# wifi-amp.net
KiCad netlist of a schematic drawn in EAGLE
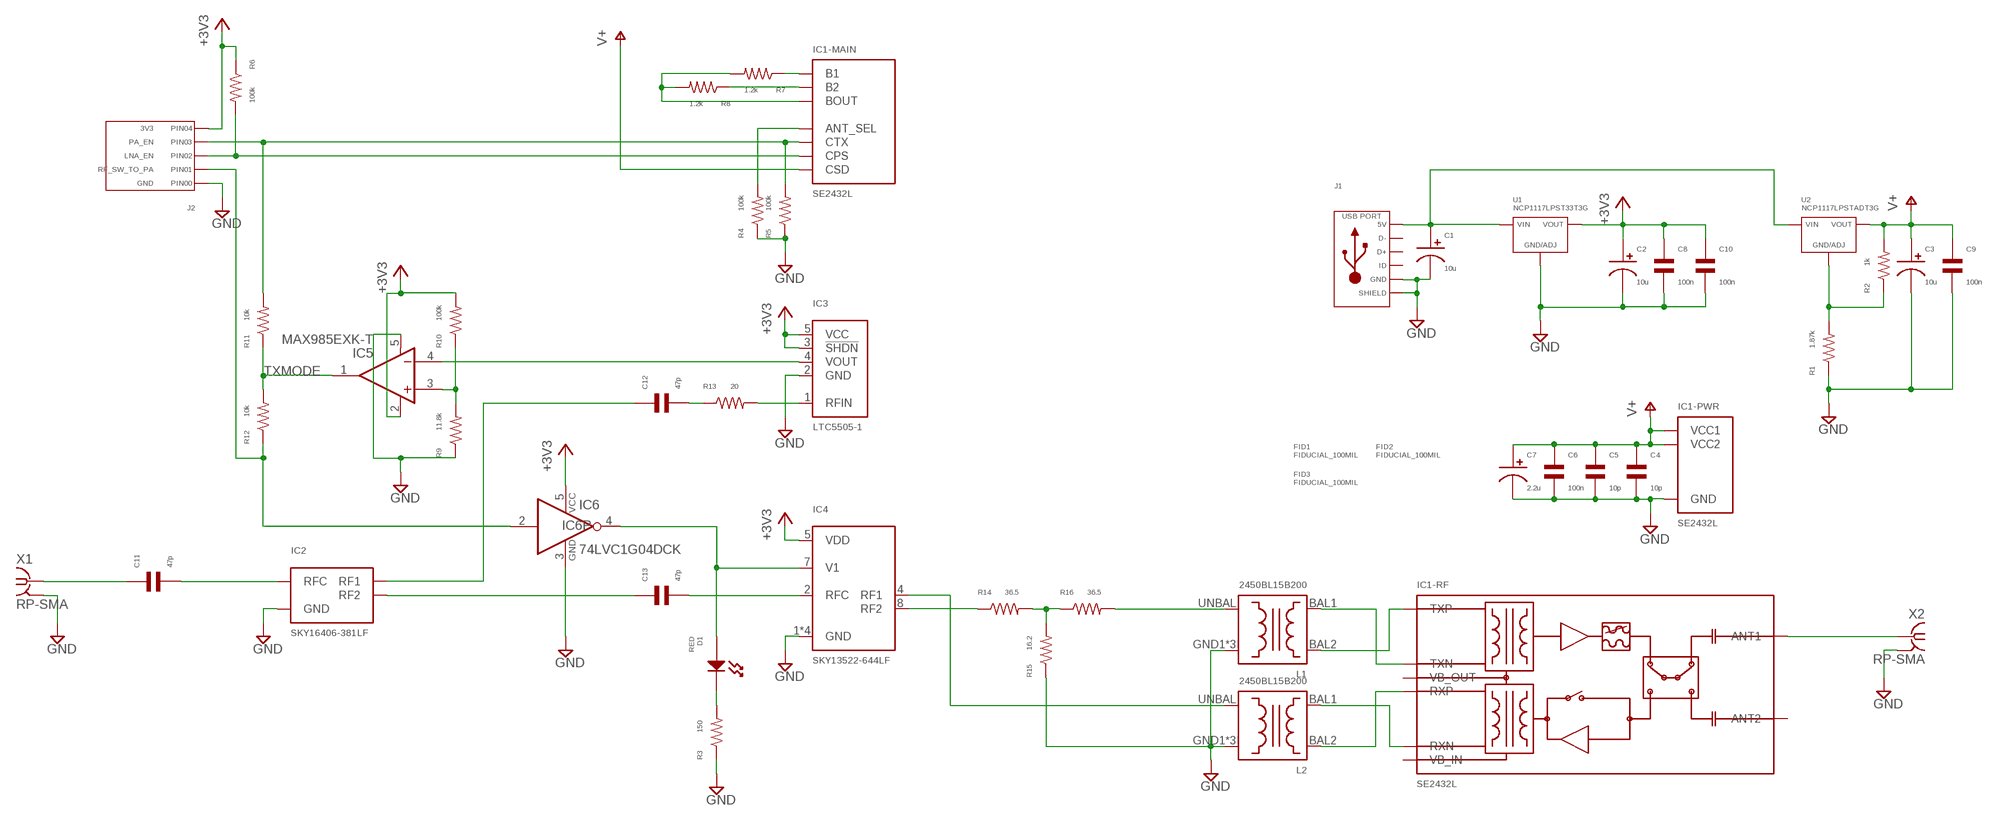
[diagram p0: schematic, sheet 1]

(export (version "E")
  (design (tool "Eeschema 10.0.6"))
  (components
    (comp (ref "C1")
      (value "10u")
      (footprint "eagle-import:CP4MM")
      (libsource (lib "eagle-import") (part "CAPACITOR_P_4MM"))
    )
    (comp (ref "C2")
      (value "10u")
      (footprint "eagle-import:CP4MM")
      (libsource (lib "eagle-import") (part "CAPACITOR_P_4MM"))
    )
    (comp (ref "C3")
      (value "10u")
      (footprint "eagle-import:CP4MM")
      (libsource (lib "eagle-import") (part "CAPACITOR_P_4MM"))
    )
    (comp (ref "C4")
      (value "10p")
      (footprint "eagle-import:C0402")
      (libsource (lib "eagle-import") (part "CAPACITOR_NP_0402"))
    )
    (comp (ref "C5")
      (value "10p")
      (footprint "eagle-import:C0402")
      (libsource (lib "eagle-import") (part "CAPACITOR_NP_0402"))
    )
    (comp (ref "C6")
      (value "100n")
      (footprint "eagle-import:C0402")
      (libsource (lib "eagle-import") (part "CAPACITOR_NP_0402"))
    )
    (comp (ref "C7")
      (value "2.2u")
      (footprint "eagle-import:CP4MM")
      (libsource (lib "eagle-import") (part "CAPACITOR_P_4MM"))
    )
    (comp (ref "C8")
      (value "100n")
      (footprint "eagle-import:C0402")
      (libsource (lib "eagle-import") (part "CAPACITOR_NP_0402"))
    )
    (comp (ref "C9")
      (value "100n")
      (footprint "eagle-import:C0402")
      (libsource (lib "eagle-import") (part "CAPACITOR_NP_0402"))
    )
    (comp (ref "C10")
      (value "100n")
      (footprint "eagle-import:C0402")
      (libsource (lib "eagle-import") (part "CAPACITOR_NP_0402"))
    )
    (comp (ref "C11")
      (value "47p")
      (footprint "eagle-import:C0402")
      (libsource (lib "eagle-import") (part "CAPACITOR_NP_0402"))
    )
    (comp (ref "C12")
      (value "47p")
      (footprint "eagle-import:C0402")
      (libsource (lib "eagle-import") (part "CAPACITOR_NP_0402"))
    )
    (comp (ref "C13")
      (value "47p")
      (footprint "eagle-import:C0402")
      (libsource (lib "eagle-import") (part "CAPACITOR_NP_0402"))
    )
    (comp (ref "D1")
      (value "RED")
      (footprint "eagle-import:LED0603")
      (libsource (lib "eagle-import") (part "LED_SINGLE_0603"))
    )
    (comp (ref "FID1")
      (value "FIDUCIAL_100MIL")
      (footprint "eagle-import:FIDUCIAL_100MIL")
      (libsource (lib "eagle-import") (part "FIDUCIAL_100MIL"))
    )
    (comp (ref "FID2")
      (value "FIDUCIAL_100MIL")
      (footprint "eagle-import:FIDUCIAL_100MIL")
      (libsource (lib "eagle-import") (part "FIDUCIAL_100MIL"))
    )
    (comp (ref "FID3")
      (value "FIDUCIAL_100MIL")
      (footprint "eagle-import:FIDUCIAL_100MIL")
      (libsource (lib "eagle-import") (part "FIDUCIAL_100MIL"))
    )
    (comp (ref "IC1")
      (value "SE2432L")
      (footprint "eagle-import:24QFN")
      (libsource (lib "eagle-import") (part "SE2432L"))
    )
    (comp (ref "IC2")
      (value "SKY16406-381LF")
      (footprint "eagle-import:DFN6")
      (libsource (lib "eagle-import") (part "SKY16406-381LF"))
    )
    (comp (ref "IC3")
      (value "LTC5505-1")
      (footprint "eagle-import:SOT23-5")
      (libsource (lib "eagle-import") (part "LTC5505"))
    )
    (comp (ref "IC4")
      (value "SKY13522-644LF")
      (footprint "eagle-import:QFN8")
      (libsource (lib "eagle-import") (part "SKY13522-644LF"))
    )
    (comp (ref "IC5")
      (value "MAX985EXK-T")
      (footprint "eagle-import:SC70-5L")
      (fields (field (name "MPN") "MAX986EXK+T"))
      (libsource (lib "eagle-import") (part "MAX98EXK-T6"))
    )
    (comp (ref "IC6")
      (value "74LVC1G04DCK")
      (footprint "eagle-import:SC70-5")
      (libsource (lib "eagle-import") (part "741G04DCKLVC"))
    )
    (comp (ref "J1")
      (value "USB_MICRO_RIGHT")
      (footprint "eagle-import:MICROUSB-RIGHT")
      (libsource (lib "eagle-import") (part "USB_MICRO_RIGHT"))
    )
    (comp (ref "J2")
      (value "HEADER_01X05_PTH_2.54MM")
      (footprint "eagle-import:PTH_2.54MM_01X05")
      (fields
        (field (name "LABEL00") "GND")
        (field (name "LABEL01") "RF_SW_TO_PA")
        (field (name "LABEL02") "LNA_EN")
        (field (name "LABEL03") "PA_EN")
        (field (name "LABEL04") "3V3")
      )
      (libsource (lib "eagle-import") (part "HEADER_01X05_PTH_2.54MM"))
    )
    (comp (ref "L1")
      (value "2450BL15B200")
      (footprint "eagle-import:2450BL15B200")
      (libsource (lib "eagle-import") (part "2450BL15B200"))
    )
    (comp (ref "L2")
      (value "2450BL15B200")
      (footprint "eagle-import:2450BL15B200")
      (libsource (lib "eagle-import") (part "2450BL15B200"))
    )
    (comp (ref "R1")
      (value "1.87k")
      (footprint "eagle-import:R0805")
      (fields (field (name "TOLERANCE") "1%"))
      (libsource (lib "eagle-import") (part "RESISTOR_0805"))
    )
    (comp (ref "R2")
      (value "1k")
      (footprint "eagle-import:R0805")
      (fields (field (name "TOLERANCE") "1%"))
      (libsource (lib "eagle-import") (part "RESISTOR_0805"))
    )
    (comp (ref "R3")
      (value "150")
      (footprint "eagle-import:R0402")
      (fields (field (name "TOLERANCE") "1%"))
      (libsource (lib "eagle-import") (part "RESISTOR_0402"))
    )
    (comp (ref "R4")
      (value "100k")
      (footprint "eagle-import:R0402")
      (libsource (lib "eagle-import") (part "RESISTOR_0402"))
    )
    (comp (ref "R5")
      (value "100k")
      (footprint "eagle-import:R0402")
      (libsource (lib "eagle-import") (part "RESISTOR_0402"))
    )
    (comp (ref "R6")
      (value "100k")
      (footprint "eagle-import:R0402")
      (libsource (lib "eagle-import") (part "RESISTOR_0402"))
    )
    (comp (ref "R7")
      (value "1.2k")
      (footprint "eagle-import:R0402")
      (fields (field (name "TOLERANCE") "1%"))
      (libsource (lib "eagle-import") (part "RESISTOR_0402"))
    )
    (comp (ref "R8")
      (value "1.2k")
      (footprint "eagle-import:R0402")
      (fields (field (name "TOLERANCE") "1%"))
      (libsource (lib "eagle-import") (part "RESISTOR_0402"))
    )
    (comp (ref "R9")
      (value "11.8k")
      (footprint "eagle-import:R0402")
      (fields (field (name "TOLERANCE") "1%"))
      (libsource (lib "eagle-import") (part "RESISTOR_0402"))
    )
    (comp (ref "R10")
      (value "100k")
      (footprint "eagle-import:R0402")
      (fields (field (name "TOLERANCE") "1%"))
      (libsource (lib "eagle-import") (part "RESISTOR_0402"))
    )
    (comp (ref "R11")
      (value "10k")
      (footprint "eagle-import:R0402")
      (libsource (lib "eagle-import") (part "RESISTOR_0402"))
    )
    (comp (ref "R12")
      (value "10k")
      (footprint "eagle-import:R0402")
      (libsource (lib "eagle-import") (part "RESISTOR_0402"))
    )
    (comp (ref "R13")
      (value "20")
      (footprint "eagle-import:R0402")
      (fields (field (name "TOLERANCE") "1%"))
      (libsource (lib "eagle-import") (part "RESISTOR_0402"))
    )
    (comp (ref "R14")
      (value "36.5")
      (footprint "eagle-import:R0402")
      (fields (field (name "TOLERANCE") "1%"))
      (libsource (lib "eagle-import") (part "RESISTOR_0402"))
    )
    (comp (ref "R15")
      (value "16.2")
      (footprint "eagle-import:R0402")
      (fields (field (name "TOLERANCE") "1%"))
      (libsource (lib "eagle-import") (part "RESISTOR_0402"))
    )
    (comp (ref "R16")
      (value "36.5")
      (footprint "eagle-import:R0402")
      (fields (field (name "TOLERANCE") "1%"))
      (libsource (lib "eagle-import") (part "RESISTOR_0402"))
    )
    (comp (ref "U1")
      (value "NCP1117LPST33T3G")
      (footprint "eagle-import:SOT-223-3")
      (libsource (lib "eagle-import") (part "NCP1117LPST33T3G"))
    )
    (comp (ref "U2")
      (value "NCP1117LPSTADT3G")
      (footprint "eagle-import:SOT-223-3")
      (libsource (lib "eagle-import") (part "NCP1117LPSTADT3G"))
    )
    (comp (ref "X1")
      (value "RP-SMA")
      (footprint "eagle-import:BU-SMA-H")
      (libsource (lib "eagle-import") (part "BU-SMA-H"))
    )
    (comp (ref "X2")
      (value "RP-SMA")
      (footprint "eagle-import:BU-SMA-H")
      (libsource (lib "eagle-import") (part "BU-SMA-H"))
    )
  )
  (nets
    (net (code "1") (name "+3V3") (class "Default")
      (node (ref "C10") (pin "P$1") (pinfunction "P$1_P$1") (pintype "passive"))
      (node (ref "C2") (pin "P$1") (pinfunction "P$1_P$1") (pintype "passive"))
      (node (ref "C8") (pin "P$1") (pinfunction "P$1_P$1") (pintype "passive"))
      (node (ref "IC3") (pin "3") (pinfunction "~{SHDN}_3") (pintype "bidirectional"))
      (node (ref "IC3") (pin "5") (pinfunction "VCC_5") (pintype "bidirectional"))
      (node (ref "IC4") (pin "5") (pinfunction "VDD_5") (pintype "bidirectional"))
      (node (ref "IC5") (pin "2") (pinfunction "V+_2") (pintype "power_in"))
      (node (ref "IC6") (pin "5") (pinfunction "VCC_5") (pintype "power_in"))
      (node (ref "J2") (pin "P$5") (pinfunction "PIN4_P$5") (pintype "bidirectional"))
      (node (ref "R10") (pin "P$2") (pinfunction "P$2_P$2") (pintype "passive"))
      (node (ref "R6") (pin "P$1") (pinfunction "P$1_P$1") (pintype "passive"))
      (node (ref "U1") (pin "P$1") (pinfunction "VOUT_P$1") (pintype "bidirectional"))
      (node (ref "U1") (pin "P$3") (pinfunction "VOUT_P$3") (pintype "bidirectional"))
    )
    (net (code "2") (name "/TXMODE") (class "Default")
      (node (ref "IC5") (pin "1") (pinfunction "OUT_1") (pintype "output"))
      (node (ref "R11") (pin "P$1") (pinfunction "P$1_P$1") (pintype "passive"))
      (node (ref "R12") (pin "P$2") (pinfunction "P$2_P$2") (pintype "passive"))
    )
    (net (code "3") (name "GND") (class "Default")
      (node (ref "C1") (pin "P$2") (pinfunction "P$2_P$2") (pintype "passive"))
      (node (ref "C10") (pin "P$2") (pinfunction "P$2_P$2") (pintype "passive"))
      (node (ref "C2") (pin "P$2") (pinfunction "P$2_P$2") (pintype "passive"))
      (node (ref "C3") (pin "P$2") (pinfunction "P$2_P$2") (pintype "passive"))
      (node (ref "C4") (pin "P$2") (pinfunction "P$2_P$2") (pintype "passive"))
      (node (ref "C5") (pin "P$2") (pinfunction "P$2_P$2") (pintype "passive"))
      (node (ref "C6") (pin "P$2") (pinfunction "P$2_P$2") (pintype "passive"))
      (node (ref "C7") (pin "P$2") (pinfunction "P$2_P$2") (pintype "passive"))
      (node (ref "C8") (pin "P$2") (pinfunction "P$2_P$2") (pintype "passive"))
      (node (ref "C9") (pin "P$2") (pinfunction "P$2_P$2") (pintype "passive"))
      (node (ref "IC1") (pin "GND1") (pinfunction "GND_GND1") (pintype "bidirectional"))
      (node (ref "IC1") (pin "GND10") (pinfunction "GND_GND10") (pintype "bidirectional"))
      (node (ref "IC1") (pin "GND2") (pinfunction "GND_GND2") (pintype "bidirectional"))
      (node (ref "IC1") (pin "GND3") (pinfunction "GND_GND3") (pintype "bidirectional"))
      (node (ref "IC1") (pin "GND4") (pinfunction "GND_GND4") (pintype "bidirectional"))
      (node (ref "IC1") (pin "GND5") (pinfunction "GND_GND5") (pintype "bidirectional"))
      (node (ref "IC1") (pin "GND6") (pinfunction "GND_GND6") (pintype "bidirectional"))
      (node (ref "IC1") (pin "GND7") (pinfunction "GND_GND7") (pintype "bidirectional"))
      (node (ref "IC1") (pin "GND8") (pinfunction "GND_GND8") (pintype "bidirectional"))
      (node (ref "IC1") (pin "GND9") (pinfunction "GND_GND9") (pintype "bidirectional"))
      (node (ref "IC2") (pin "GND1") (pinfunction "GND_GND1") (pintype "bidirectional"))
      (node (ref "IC2") (pin "GND2") (pinfunction "GND_GND2") (pintype "bidirectional"))
      (node (ref "IC2") (pin "GND3") (pinfunction "GND_GND3") (pintype "bidirectional"))
      (node (ref "IC2") (pin "GNDP") (pinfunction "GND_GNDP") (pintype "bidirectional"))
      (node (ref "IC3") (pin "2") (pinfunction "GND_2") (pintype "bidirectional"))
      (node (ref "IC4") (pin "1") (pinfunction "GND_1") (pintype "bidirectional"))
      (node (ref "IC4") (pin "3") (pinfunction "GND_3") (pintype "bidirectional"))
      (node (ref "IC4") (pin "6") (pinfunction "GND_6") (pintype "bidirectional"))
      (node (ref "IC4") (pin "EP") (pinfunction "GND_EP") (pintype "bidirectional"))
      (node (ref "IC5") (pin "5") (pinfunction "V-_5") (pintype "power_in"))
      (node (ref "IC6") (pin "3") (pinfunction "GND_3") (pintype "power_in"))
      (node (ref "J1") (pin "5") (pinfunction "GND_5") (pintype "power_in"))
      (node (ref "J1") (pin "S1") (pinfunction "SLD_S1") (pintype "power_in"))
      (node (ref "J1") (pin "S2") (pinfunction "SLD_S2") (pintype "power_in"))
      (node (ref "J1") (pin "S3") (pinfunction "SLD_S3") (pintype "power_in"))
      (node (ref "J1") (pin "S4") (pinfunction "SLD_S4") (pintype "power_in"))
      (node (ref "J1") (pin "S5") (pinfunction "SLD_S5") (pintype "power_in"))
      (node (ref "J1") (pin "S6") (pinfunction "SLD_S6") (pintype "power_in"))
      (node (ref "J1") (pin "S7") (pinfunction "SLD_S7") (pintype "power_in"))
      (node (ref "J1") (pin "S8") (pinfunction "SLD_S8") (pintype "power_in"))
      (node (ref "J2") (pin "P$1") (pinfunction "PIN0_P$1") (pintype "bidirectional"))
      (node (ref "L1") (pin "GND1") (pinfunction "GND_GND1") (pintype "bidirectional"))
      (node (ref "L1") (pin "GND2") (pinfunction "GND_GND2") (pintype "bidirectional"))
      (node (ref "L1") (pin "GND3") (pinfunction "GND_GND3") (pintype "bidirectional"))
      (node (ref "L2") (pin "GND1") (pinfunction "GND_GND1") (pintype "bidirectional"))
      (node (ref "L2") (pin "GND2") (pinfunction "GND_GND2") (pintype "bidirectional"))
      (node (ref "L2") (pin "GND3") (pinfunction "GND_GND3") (pintype "bidirectional"))
      (node (ref "R1") (pin "P$1") (pinfunction "P$1_P$1") (pintype "passive"))
      (node (ref "R15") (pin "P$1") (pinfunction "P$1_P$1") (pintype "passive"))
      (node (ref "R3") (pin "P$1") (pinfunction "P$1_P$1") (pintype "passive"))
      (node (ref "R4") (pin "P$1") (pinfunction "P$1_P$1") (pintype "passive"))
      (node (ref "R5") (pin "P$1") (pinfunction "P$1_P$1") (pintype "passive"))
      (node (ref "R9") (pin "P$1") (pinfunction "P$1_P$1") (pintype "passive"))
      (node (ref "U1") (pin "P$2") (pinfunction "GND/ADJ_P$2") (pintype "bidirectional"))
      (node (ref "X1") (pin "2") (pinfunction "2_2") (pintype "passive"))
      (node (ref "X1") (pin "3") (pinfunction "2_3") (pintype "passive"))
      (node (ref "X1") (pin "4") (pinfunction "2_4") (pintype "passive"))
      (node (ref "X1") (pin "5") (pinfunction "2_5") (pintype "passive"))
      (node (ref "X2") (pin "2") (pinfunction "2_2") (pintype "passive"))
      (node (ref "X2") (pin "3") (pinfunction "2_3") (pintype "passive"))
      (node (ref "X2") (pin "4") (pinfunction "2_4") (pintype "passive"))
      (node (ref "X2") (pin "5") (pinfunction "2_5") (pintype "passive"))
    )
    (net (code "4") (name "Net-(C11-PadP$1)") (class "Default")
      (node (ref "C11") (pin "P$1") (pinfunction "P$1_P$1") (pintype "passive"))
      (node (ref "X1") (pin "1") (pinfunction "1_1") (pintype "passive"))
    )
    (net (code "5") (name "Net-(C11-PadP$2)") (class "Default")
      (node (ref "C11") (pin "P$2") (pinfunction "P$2_P$2") (pintype "passive"))
      (node (ref "IC2") (pin "RFC") (pinfunction "RFC_RFC") (pintype "bidirectional"))
    )
    (net (code "6") (name "Net-(C12-PadP$1)") (class "Default")
      (node (ref "C12") (pin "P$1") (pinfunction "P$1_P$1") (pintype "passive"))
      (node (ref "IC2") (pin "RF1") (pinfunction "RF1_RF1") (pintype "bidirectional"))
    )
    (net (code "7") (name "Net-(C12-PadP$2)") (class "Default")
      (node (ref "C12") (pin "P$2") (pinfunction "P$2_P$2") (pintype "passive"))
      (node (ref "R13") (pin "P$1") (pinfunction "P$1_P$1") (pintype "passive"))
    )
    (net (code "8") (name "Net-(C13-PadP$1)") (class "Default")
      (node (ref "C13") (pin "P$1") (pinfunction "P$1_P$1") (pintype "passive"))
      (node (ref "IC2") (pin "RF2") (pinfunction "RF2_RF2") (pintype "bidirectional"))
    )
    (net (code "9") (name "Net-(D1-PadCATHODE)") (class "Default")
      (node (ref "D1") (pin "CATHODE") (pinfunction "CATHODE_CATHODE") (pintype "power_in"))
      (node (ref "R3") (pin "P$2") (pinfunction "P$2_P$2") (pintype "passive"))
    )
    (net (code "10") (name "Net-(IC1-PadANT1)") (class "Default")
      (node (ref "IC1") (pin "ANT1") (pinfunction "ANT1_ANT1") (pintype "bidirectional"))
      (node (ref "X2") (pin "1") (pinfunction "1_1") (pintype "passive"))
    )
    (net (code "11") (name "Net-(IC1-PadANT_SEL)") (class "Default")
      (node (ref "IC1") (pin "ANT_SEL") (pinfunction "ANT_SEL_ANT_SEL") (pintype "bidirectional"))
      (node (ref "R4") (pin "P$2") (pinfunction "P$2_P$2") (pintype "passive"))
    )
    (net (code "12") (name "Net-(IC1-PadB1)") (class "Default")
      (node (ref "IC1") (pin "B1") (pinfunction "B1_B1") (pintype "bidirectional"))
      (node (ref "R7") (pin "P$1") (pinfunction "P$1_P$1") (pintype "passive"))
    )
    (net (code "13") (name "Net-(IC1-PadB2)") (class "Default")
      (node (ref "IC1") (pin "B2") (pinfunction "B2_B2") (pintype "bidirectional"))
      (node (ref "R8") (pin "P$1") (pinfunction "P$1_P$1") (pintype "passive"))
    )
    (net (code "14") (name "Net-(IC1-PadBOUT)") (class "Default")
      (node (ref "IC1") (pin "BOUT") (pinfunction "BOUT_BOUT") (pintype "bidirectional"))
      (node (ref "R7") (pin "P$2") (pinfunction "P$2_P$2") (pintype "passive"))
      (node (ref "R8") (pin "P$2") (pinfunction "P$2_P$2") (pintype "passive"))
    )
    (net (code "15") (name "Net-(IC1-PadRXN)") (class "Default")
      (node (ref "IC1") (pin "RXN") (pinfunction "RXN_RXN") (pintype "bidirectional"))
      (node (ref "L2") (pin "BAL1") (pinfunction "BAL1_BAL1") (pintype "bidirectional"))
    )
    (net (code "16") (name "Net-(IC1-PadRXP)") (class "Default")
      (node (ref "IC1") (pin "RXP") (pinfunction "RXP_RXP") (pintype "bidirectional"))
      (node (ref "L2") (pin "BAL2") (pinfunction "BAL2_BAL2") (pintype "bidirectional"))
    )
    (net (code "17") (name "Net-(IC1-PadTXN)") (class "Default")
      (node (ref "IC1") (pin "TXN") (pinfunction "TXN_TXN") (pintype "bidirectional"))
      (node (ref "L1") (pin "BAL1") (pinfunction "BAL1_BAL1") (pintype "bidirectional"))
    )
    (net (code "18") (name "Net-(IC1-PadTXP)") (class "Default")
      (node (ref "IC1") (pin "TXP") (pinfunction "TXP_TXP") (pintype "bidirectional"))
      (node (ref "L1") (pin "BAL2") (pinfunction "BAL2_BAL2") (pintype "bidirectional"))
    )
    (net (code "19") (name "Net-(IC3-RFIN)") (class "Default")
      (node (ref "IC3") (pin "1") (pinfunction "RFIN_1") (pintype "bidirectional"))
      (node (ref "R13") (pin "P$2") (pinfunction "P$2_P$2") (pintype "passive"))
    )
    (net (code "20") (name "Net-(IC3-VOUT)") (class "Default")
      (node (ref "IC3") (pin "4") (pinfunction "VOUT_4") (pintype "bidirectional"))
      (node (ref "IC5") (pin "4") (pinfunction "-IN_4") (pintype "input"))
    )
    (net (code "21") (name "Net-(IC4-RF1)") (class "Default")
      (node (ref "IC4") (pin "4") (pinfunction "RF1_4") (pintype "bidirectional"))
      (node (ref "L2") (pin "UNBAL") (pinfunction "UNBAL_UNBAL") (pintype "bidirectional"))
    )
    (net (code "22") (name "Net-(IC4-RF2)") (class "Default")
      (node (ref "IC4") (pin "8") (pinfunction "RF2_8") (pintype "bidirectional"))
      (node (ref "R14") (pin "P$1") (pinfunction "P$1_P$1") (pintype "passive"))
    )
    (net (code "23") (name "Net-(IC4-RFC)") (class "Default")
      (node (ref "C13") (pin "P$2") (pinfunction "P$2_P$2") (pintype "passive"))
      (node (ref "IC4") (pin "2") (pinfunction "RFC_2") (pintype "bidirectional"))
    )
    (net (code "24") (name "Net-(IC4-V1)") (class "Default")
      (node (ref "D1") (pin "ANODE") (pinfunction "ANODE_ANODE") (pintype "power_in"))
      (node (ref "IC4") (pin "7") (pinfunction "V1_7") (pintype "bidirectional"))
      (node (ref "IC6") (pin "4") (pinfunction "O_4") (pintype "output"))
    )
    (net (code "25") (name "Net-(IC5-+IN)") (class "Default")
      (node (ref "IC5") (pin "3") (pinfunction "+IN_3") (pintype "input"))
      (node (ref "R10") (pin "P$1") (pinfunction "P$1_P$1") (pintype "passive"))
      (node (ref "R9") (pin "P$2") (pinfunction "P$2_P$2") (pintype "passive"))
    )
    (net (code "26") (name "Net-(IC6A-I)") (class "Default")
      (node (ref "IC6") (pin "2") (pinfunction "I_2") (pintype "input"))
      (node (ref "J2") (pin "P$2") (pinfunction "PIN1_P$2") (pintype "bidirectional"))
      (node (ref "R12") (pin "P$1") (pinfunction "P$1_P$1") (pintype "passive"))
    )
    (net (code "27") (name "Net-(J1-5V)") (class "Default")
      (node (ref "C1") (pin "P$1") (pinfunction "P$1_P$1") (pintype "passive"))
      (node (ref "J1") (pin "1") (pinfunction "5V_1") (pintype "power_in"))
      (node (ref "U1") (pin "P$4") (pinfunction "VIN_P$4") (pintype "bidirectional"))
      (node (ref "U2") (pin "P$4") (pinfunction "VIN_P$4") (pintype "bidirectional"))
    )
    (net (code "28") (name "Net-(J2-PIN2)") (class "Default")
      (node (ref "IC1") (pin "CPS") (pinfunction "CPS_CPS") (pintype "bidirectional"))
      (node (ref "J2") (pin "P$3") (pinfunction "PIN2_P$3") (pintype "bidirectional"))
      (node (ref "R6") (pin "P$2") (pinfunction "P$2_P$2") (pintype "passive"))
    )
    (net (code "29") (name "Net-(J2-PIN3)") (class "Default")
      (node (ref "IC1") (pin "CTX") (pinfunction "CTX_CTX") (pintype "bidirectional"))
      (node (ref "J2") (pin "P$4") (pinfunction "PIN3_P$4") (pintype "bidirectional"))
      (node (ref "R11") (pin "P$2") (pinfunction "P$2_P$2") (pintype "passive"))
      (node (ref "R5") (pin "P$2") (pinfunction "P$2_P$2") (pintype "passive"))
    )
    (net (code "30") (name "Net-(L1-PadUNBAL)") (class "Default")
      (node (ref "L1") (pin "UNBAL") (pinfunction "UNBAL_UNBAL") (pintype "bidirectional"))
      (node (ref "R16") (pin "P$2") (pinfunction "P$2_P$2") (pintype "passive"))
    )
    (net (code "31") (name "Net-(R14-PadP$2)") (class "Default")
      (node (ref "R14") (pin "P$2") (pinfunction "P$2_P$2") (pintype "passive"))
      (node (ref "R15") (pin "P$2") (pinfunction "P$2_P$2") (pintype "passive"))
      (node (ref "R16") (pin "P$1") (pinfunction "P$1_P$1") (pintype "passive"))
    )
    (net (code "32") (name "Net-(U2-GND{slash}ADJ)") (class "Default")
      (node (ref "R1") (pin "P$2") (pinfunction "P$2_P$2") (pintype "passive"))
      (node (ref "R2") (pin "P$1") (pinfunction "P$1_P$1") (pintype "passive"))
      (node (ref "U2") (pin "P$2") (pinfunction "GND/ADJ_P$2") (pintype "bidirectional"))
    )
    (net (code "33") (name "V+") (class "Default")
      (node (ref "C3") (pin "P$1") (pinfunction "P$1_P$1") (pintype "passive"))
      (node (ref "C4") (pin "P$1") (pinfunction "P$1_P$1") (pintype "passive"))
      (node (ref "C5") (pin "P$1") (pinfunction "P$1_P$1") (pintype "passive"))
      (node (ref "C6") (pin "P$1") (pinfunction "P$1_P$1") (pintype "passive"))
      (node (ref "C7") (pin "P$1") (pinfunction "P$1_P$1") (pintype "passive"))
      (node (ref "C9") (pin "P$1") (pinfunction "P$1_P$1") (pintype "passive"))
      (node (ref "IC1") (pin "CSD") (pinfunction "CSD_CSD") (pintype "bidirectional"))
      (node (ref "IC1") (pin "VCC1") (pinfunction "VCC1_VCC1") (pintype "bidirectional"))
      (node (ref "IC1") (pin "VCC2") (pinfunction "VCC2_VCC2") (pintype "bidirectional"))
      (node (ref "R2") (pin "P$2") (pinfunction "P$2_P$2") (pintype "passive"))
      (node (ref "U2") (pin "P$1") (pinfunction "VOUT_P$1") (pintype "bidirectional"))
      (node (ref "U2") (pin "P$3") (pinfunction "VOUT_P$3") (pintype "bidirectional"))
    )
    (net (code "34") (name "unconnected-(IC1-PadANT2)") (class "Default")
      (node (ref "IC1") (pin "ANT2") (pinfunction "ANT2_ANT2") (pintype "bidirectional"))
    )
    (net (code "35") (name "unconnected-(IC1-PadVB_IN)") (class "Default")
      (node (ref "IC1") (pin "VB_IN") (pinfunction "VB_IN_VB_IN") (pintype "bidirectional"))
    )
    (net (code "36") (name "unconnected-(IC1-PadVB_OUT)") (class "Default")
      (node (ref "IC1") (pin "VB_OUT") (pinfunction "VB_OUT_VB_OUT") (pintype "bidirectional"))
    )
    (net (code "37") (name "unconnected-(J1-D+-Pad3)") (class "Default")
      (node (ref "J1") (pin "3") (pinfunction "D+_3") (pintype "bidirectional"))
    )
    (net (code "38") (name "unconnected-(J1-D--Pad2)") (class "Default")
      (node (ref "J1") (pin "2") (pinfunction "D-_2") (pintype "bidirectional"))
    )
    (net (code "39") (name "unconnected-(J1-ID-Pad4)") (class "Default")
      (node (ref "J1") (pin "4") (pinfunction "ID_4") (pintype "bidirectional"))
    )
  )
)
